# accelerometer.net
KiCad netlist of a schematic drawn in Altium Designer
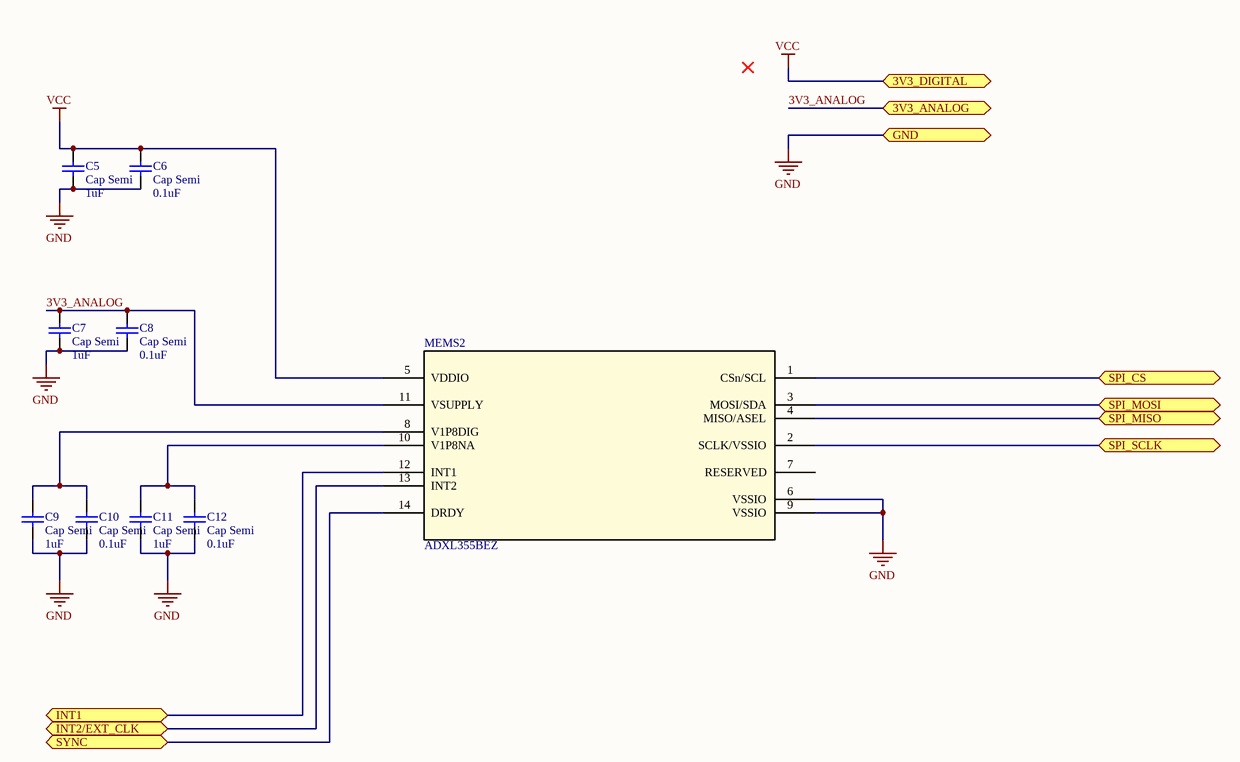
[diagram p0: accelerometer.SchDoc]

(export (version "E")
  (design (tool "Eeschema 10.0.6"))
  (components
    (comp (ref "C5")
      (value "Cap Semi")
      (footprint "C1210")
      (description "Capacitor (Semiconductor SIM Model)")
      (fields (field (name "ALTIUM_VALUE") "1uF") (field (name "PUBLISHER") "Altium Limited"))
      (libsource (lib "Miscellaneous Devices") (part "Cap Semi"))
    )
    (comp (ref "C6")
      (value "Cap Semi")
      (footprint "C1206")
      (description "Capacitor (Semiconductor SIM Model)")
      (fields (field (name "ALTIUM_VALUE") "0.1uF") (field (name "PUBLISHER") "Altium Limited"))
      (libsource (lib "Miscellaneous Devices") (part "Cap Semi"))
    )
    (comp (ref "C7")
      (value "Cap Semi")
      (footprint "C1210")
      (description "Capacitor (Semiconductor SIM Model)")
      (fields (field (name "ALTIUM_VALUE") "1uF") (field (name "PUBLISHER") "Altium Limited"))
      (libsource (lib "Miscellaneous Devices") (part "Cap Semi"))
    )
    (comp (ref "C8")
      (value "Cap Semi")
      (footprint "C1206")
      (description "Capacitor (Semiconductor SIM Model)")
      (fields (field (name "ALTIUM_VALUE") "0.1uF") (field (name "PUBLISHER") "Altium Limited"))
      (libsource (lib "Miscellaneous Devices") (part "Cap Semi"))
    )
    (comp (ref "C9")
      (value "Cap Semi")
      (footprint "C1210")
      (description "Capacitor (Semiconductor SIM Model)")
      (fields (field (name "ALTIUM_VALUE") "1uF") (field (name "PUBLISHER") "Altium Limited"))
      (libsource (lib "Miscellaneous Devices") (part "Cap Semi"))
    )
    (comp (ref "C10")
      (value "Cap Semi")
      (footprint "C1206")
      (description "Capacitor (Semiconductor SIM Model)")
      (fields (field (name "ALTIUM_VALUE") "0.1uF") (field (name "PUBLISHER") "Altium Limited"))
      (libsource (lib "Miscellaneous Devices") (part "Cap Semi"))
    )
    (comp (ref "C11")
      (value "Cap Semi")
      (footprint "C1210")
      (description "Capacitor (Semiconductor SIM Model)")
      (fields (field (name "ALTIUM_VALUE") "1uF") (field (name "PUBLISHER") "Altium Limited"))
      (libsource (lib "Miscellaneous Devices") (part "Cap Semi"))
    )
    (comp (ref "C12")
      (value "Cap Semi")
      (footprint "C1206")
      (description "Capacitor (Semiconductor SIM Model)")
      (fields (field (name "ALTIUM_VALUE") "0.1uF") (field (name "PUBLISHER") "Altium Limited"))
      (libsource (lib "Miscellaneous Devices") (part "Cap Semi"))
    )
    (comp (ref "MEMS2")
      (value "ADXL355BEZ")
      (footprint "E_14_1")
      (description "Imported")
      (libsource (lib "RPi_sensor_expansion_board_library") (part "ADXL355BEZ"))
    )
  )
  (nets
    (net (code "1") (name "/3V3_ANALOG") (class "Default")
      (node (ref "C7") (pin "2") (pinfunction "2_2") (pintype "passive"))
      (node (ref "C8") (pin "2") (pinfunction "2_2") (pintype "passive"))
      (node (ref "MEMS2") (pin "11") (pinfunction "VSUPPLY_11") (pintype "passive"))
    )
    (net (code "2") (name "/INT1") (class "Default")
      (node (ref "MEMS2") (pin "12") (pinfunction "INT1_12") (pintype "passive"))
    )
    (net (code "3") (name "/INT2{slash}EXT_CLK") (class "Default")
      (node (ref "MEMS2") (pin "13") (pinfunction "INT2_13") (pintype "passive"))
    )
    (net (code "4") (name "/SPI_CS") (class "Default")
      (node (ref "MEMS2") (pin "1") (pinfunction "CSn/SCL_1") (pintype "passive"))
    )
    (net (code "5") (name "/SPI_MISO") (class "Default")
      (node (ref "MEMS2") (pin "4") (pinfunction "MISO/ASEL_4") (pintype "passive"))
    )
    (net (code "6") (name "/SPI_MOSI") (class "Default")
      (node (ref "MEMS2") (pin "3") (pinfunction "MOSI/SDA_3") (pintype "passive"))
    )
    (net (code "7") (name "/SPI_SCLK") (class "Default")
      (node (ref "MEMS2") (pin "2") (pinfunction "SCLK/VSSIO_2") (pintype "passive"))
    )
    (net (code "8") (name "/SYNC") (class "Default")
      (node (ref "MEMS2") (pin "14") (pinfunction "DRDY_14") (pintype "passive"))
    )
    (net (code "9") (name "GND") (class "Default")
      (node (ref "C10") (pin "1") (pinfunction "1_1") (pintype "passive"))
      (node (ref "C11") (pin "1") (pinfunction "1_1") (pintype "passive"))
      (node (ref "C12") (pin "1") (pinfunction "1_1") (pintype "passive"))
      (node (ref "C5") (pin "1") (pinfunction "1_1") (pintype "passive"))
      (node (ref "C6") (pin "1") (pinfunction "1_1") (pintype "passive"))
      (node (ref "C7") (pin "1") (pinfunction "1_1") (pintype "passive"))
      (node (ref "C8") (pin "1") (pinfunction "1_1") (pintype "passive"))
      (node (ref "C9") (pin "1") (pinfunction "1_1") (pintype "passive"))
      (node (ref "MEMS2") (pin "6") (pinfunction "VSSIO_6") (pintype "passive"))
      (node (ref "MEMS2") (pin "9") (pinfunction "VSSIO_9") (pintype "passive"))
    )
    (net (code "10") (name "Net-(MEMS2-V1P8DIG)") (class "Default")
      (node (ref "C10") (pin "2") (pinfunction "2_2") (pintype "passive"))
      (node (ref "C9") (pin "2") (pinfunction "2_2") (pintype "passive"))
      (node (ref "MEMS2") (pin "8") (pinfunction "V1P8DIG_8") (pintype "passive"))
    )
    (net (code "11") (name "Net-(MEMS2-V1P8NA)") (class "Default")
      (node (ref "C11") (pin "2") (pinfunction "2_2") (pintype "passive"))
      (node (ref "C12") (pin "2") (pinfunction "2_2") (pintype "passive"))
      (node (ref "MEMS2") (pin "10") (pinfunction "V1P8NA_10") (pintype "passive"))
    )
    (net (code "12") (name "VCC") (class "Default")
      (node (ref "C5") (pin "2") (pinfunction "2_2") (pintype "passive"))
      (node (ref "C6") (pin "2") (pinfunction "2_2") (pintype "passive"))
      (node (ref "MEMS2") (pin "5") (pinfunction "VDDIO_5") (pintype "passive"))
    )
    (net (code "13") (name "unconnected-(MEMS2-RESERVED-Pad7)") (class "Default")
      (node (ref "MEMS2") (pin "7") (pinfunction "RESERVED_7") (pintype "passive"))
    )
  )
)
